# 34_14.net
KiCad netlist of a schematic drawn in Altium Designer
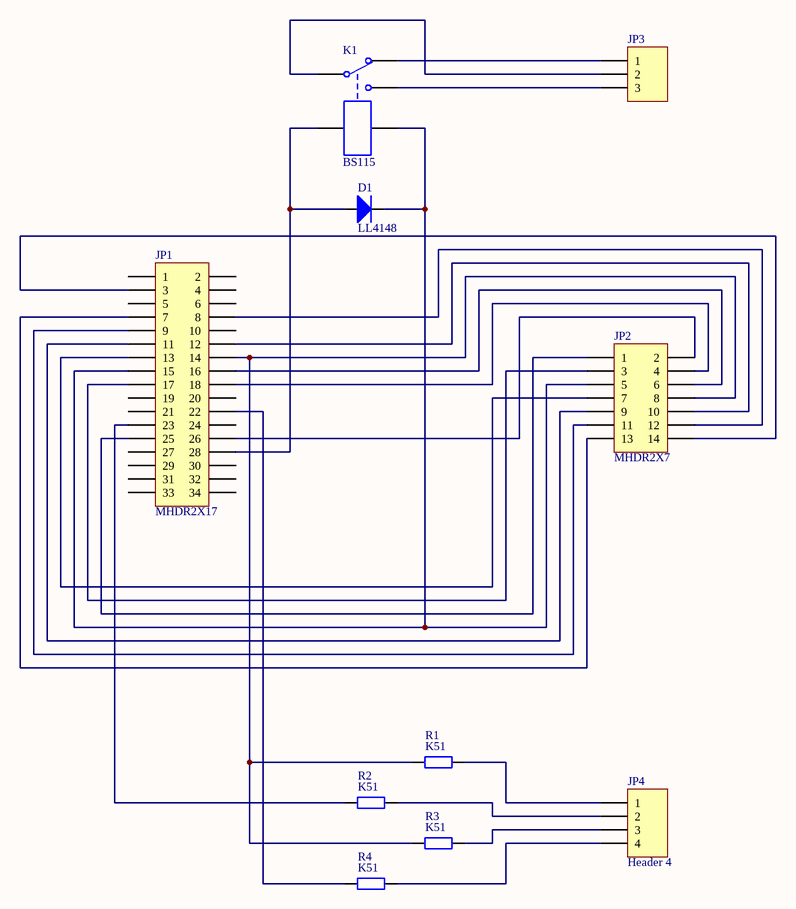
[diagram p0: 34_14.SchDoc]

(export (version "E")
  (design (tool "Eeschema 10.0.6"))
  (components
    (comp (ref "D1")
      (value "LL4148")
      (footprint "_1206d")
      (description "Diode")
      (fields (field (name "MANUFACTURER") "Generic Components") (field (name "PUBLISHER") "Altium Limited"))
      (libsource (lib "PAL") (part "Diode"))
    )
    (comp (ref "JP1")
      (value "MHDR2X17")
      (footprint "HDR2X17")
      (description "Header, 17-Pin, Dual row")
      (fields (field (name "MANUFACTURER") "Generic Components") (field (name "PUBLISHER") "Altium Limited"))
      (libsource (lib "Miscellaneous Connectors") (part "MHDR2X17"))
    )
    (comp (ref "JP2")
      (value "MHDR2X7")
      (footprint "HDR2X7")
      (description "Header, 7-Pin, Dual row")
      (fields (field (name "MANUFACTURER") "Generic Components") (field (name "PUBLISHER") "Altium Limited"))
      (libsource (lib "Miscellaneous Connectors") (part "MHDR2X7"))
    )
    (comp (ref "JP3")
      (value "Header 3")
      (footprint "2EDG-5.08-3P")
      (description "Header, 3-Pin")
      (fields (field (name "MANUFACTURER") "Generic Components") (field (name "PUBLISHER") "Altium Limited"))
      (libsource (lib "Miscellaneous Connectors") (part "Header 3"))
    )
    (comp (ref "JP4")
      (value "Header 4")
      (footprint "2EDG-5.08-4P - duplicate")
      (description "Header, 4-Pin")
      (fields (field (name "MANUFACTURER") "Generic Components") (field (name "PUBLISHER") "Altium Limited"))
      (libsource (lib "Miscellaneous Connectors") (part "Header 4"))
    )
    (comp (ref "K1")
      (value "BS115")
      (footprint "bs115")
      (description "Single-Pole Dual-Throw Relay")
      (fields (field (name "MANUFACTURER") "Generic Components") (field (name "PUBLISHER") "Altium Limited"))
      (libsource (lib "PAL") (part "BS115"))
    )
    (comp (ref "R1")
      (value "K51")
      (footprint "_1206")
      (description "Resistor")
      (fields (field (name "MANUFACTURER") "Generic Components") (field (name "PUBLISHER") "Altium Limited"))
      (libsource (lib "Miscellaneous Devices") (part "Res2"))
    )
    (comp (ref "R2")
      (value "K51")
      (footprint "_1206")
      (description "Resistor")
      (fields (field (name "MANUFACTURER") "Generic Components") (field (name "PUBLISHER") "Altium Limited"))
      (libsource (lib "Miscellaneous Devices") (part "Res2"))
    )
    (comp (ref "R3")
      (value "K51")
      (footprint "_1206")
      (description "Resistor")
      (fields (field (name "MANUFACTURER") "Generic Components") (field (name "PUBLISHER") "Altium Limited"))
      (libsource (lib "Miscellaneous Devices") (part "Res2"))
    )
    (comp (ref "R4")
      (value "K51")
      (footprint "_1206")
      (description "Resistor")
      (fields (field (name "MANUFACTURER") "Generic Components") (field (name "PUBLISHER") "Altium Limited"))
      (libsource (lib "Miscellaneous Devices") (part "Res2"))
    )
  )
  (nets
    (net (code "1") (name "Net-(D1-A)") (class "Default")
      (node (ref "D1") (pin "1") (pinfunction "A_1") (pintype "passive"))
      (node (ref "JP1") (pin "28") (pinfunction "28_28") (pintype "passive"))
      (node (ref "K1") (pin "4") (pinfunction "4_4") (pintype "passive"))
    )
    (net (code "2") (name "Net-(D1-K)") (class "Default")
      (node (ref "D1") (pin "2") (pinfunction "K_2") (pintype "passive"))
      (node (ref "JP1") (pin "15") (pinfunction "15_15") (pintype "passive"))
      (node (ref "JP2") (pin "5") (pinfunction "5_5") (pintype "passive"))
      (node (ref "K1") (pin "5") (pinfunction "5_5") (pintype "passive"))
    )
    (net (code "3") (name "Net-(JP1-Pad3)") (class "Default")
      (node (ref "JP1") (pin "3") (pinfunction "3_3") (pintype "passive"))
      (node (ref "JP2") (pin "14") (pinfunction "14_14") (pintype "passive"))
    )
    (net (code "4") (name "Net-(JP1-Pad7)") (class "Default")
      (node (ref "JP1") (pin "7") (pinfunction "7_7") (pintype "passive"))
      (node (ref "JP2") (pin "13") (pinfunction "13_13") (pintype "passive"))
    )
    (net (code "5") (name "Net-(JP1-Pad8)") (class "Default")
      (node (ref "JP1") (pin "8") (pinfunction "8_8") (pintype "passive"))
      (node (ref "JP2") (pin "12") (pinfunction "12_12") (pintype "passive"))
    )
    (net (code "6") (name "Net-(JP1-Pad9)") (class "Default")
      (node (ref "JP1") (pin "9") (pinfunction "9_9") (pintype "passive"))
      (node (ref "JP2") (pin "11") (pinfunction "11_11") (pintype "passive"))
    )
    (net (code "7") (name "Net-(JP1-Pad11)") (class "Default")
      (node (ref "JP1") (pin "11") (pinfunction "11_11") (pintype "passive"))
      (node (ref "JP2") (pin "9") (pinfunction "9_9") (pintype "passive"))
    )
    (net (code "8") (name "Net-(JP1-Pad12)") (class "Default")
      (node (ref "JP1") (pin "12") (pinfunction "12_12") (pintype "passive"))
      (node (ref "JP2") (pin "10") (pinfunction "10_10") (pintype "passive"))
    )
    (net (code "9") (name "Net-(JP1-Pad13)") (class "Default")
      (node (ref "JP1") (pin "13") (pinfunction "13_13") (pintype "passive"))
      (node (ref "JP2") (pin "7") (pinfunction "7_7") (pintype "passive"))
    )
    (net (code "10") (name "Net-(JP1-Pad14)") (class "Default")
      (node (ref "JP1") (pin "14") (pinfunction "14_14") (pintype "passive"))
      (node (ref "JP2") (pin "8") (pinfunction "8_8") (pintype "passive"))
      (node (ref "R1") (pin "1") (pinfunction "1_1") (pintype "passive"))
      (node (ref "R3") (pin "1") (pinfunction "1_1") (pintype "passive"))
    )
    (net (code "11") (name "Net-(JP1-Pad16)") (class "Default")
      (node (ref "JP1") (pin "16") (pinfunction "16_16") (pintype "passive"))
      (node (ref "JP2") (pin "6") (pinfunction "6_6") (pintype "passive"))
    )
    (net (code "12") (name "Net-(JP1-Pad17)") (class "Default")
      (node (ref "JP1") (pin "17") (pinfunction "17_17") (pintype "passive"))
      (node (ref "JP2") (pin "3") (pinfunction "3_3") (pintype "passive"))
    )
    (net (code "13") (name "Net-(JP1-Pad18)") (class "Default")
      (node (ref "JP1") (pin "18") (pinfunction "18_18") (pintype "passive"))
      (node (ref "JP2") (pin "4") (pinfunction "4_4") (pintype "passive"))
    )
    (net (code "14") (name "Net-(JP1-Pad22)") (class "Default")
      (node (ref "JP1") (pin "22") (pinfunction "22_22") (pintype "passive"))
      (node (ref "R4") (pin "1") (pinfunction "1_1") (pintype "passive"))
    )
    (net (code "15") (name "Net-(JP1-Pad23)") (class "Default")
      (node (ref "JP1") (pin "23") (pinfunction "23_23") (pintype "passive"))
      (node (ref "R2") (pin "1") (pinfunction "1_1") (pintype "passive"))
    )
    (net (code "16") (name "Net-(JP1-Pad25)") (class "Default")
      (node (ref "JP1") (pin "25") (pinfunction "25_25") (pintype "passive"))
      (node (ref "JP2") (pin "1") (pinfunction "1_1") (pintype "passive"))
    )
    (net (code "17") (name "Net-(JP1-Pad26)") (class "Default")
      (node (ref "JP1") (pin "26") (pinfunction "26_26") (pintype "passive"))
      (node (ref "JP2") (pin "2") (pinfunction "2_2") (pintype "passive"))
    )
    (net (code "18") (name "Net-(JP3-Pad1)") (class "Default")
      (node (ref "JP3") (pin "1") (pinfunction "1_1") (pintype "passive"))
      (node (ref "K1") (pin "2") (pinfunction "2_2") (pintype "passive"))
    )
    (net (code "19") (name "Net-(JP3-Pad2)") (class "Default")
      (node (ref "JP3") (pin "2") (pinfunction "2_2") (pintype "passive"))
      (node (ref "K1") (pin "1") (pinfunction "1_1") (pintype "passive"))
    )
    (net (code "20") (name "Net-(JP3-Pad3)") (class "Default")
      (node (ref "JP3") (pin "3") (pinfunction "3_3") (pintype "passive"))
      (node (ref "K1") (pin "3") (pinfunction "3_3") (pintype "passive"))
    )
    (net (code "21") (name "Net-(JP4-Pad1)") (class "Default")
      (node (ref "JP4") (pin "1") (pinfunction "1_1") (pintype "passive"))
      (node (ref "R1") (pin "2") (pinfunction "2_2") (pintype "passive"))
    )
    (net (code "22") (name "Net-(JP4-Pad2)") (class "Default")
      (node (ref "JP4") (pin "2") (pinfunction "2_2") (pintype "passive"))
      (node (ref "R2") (pin "2") (pinfunction "2_2") (pintype "passive"))
    )
    (net (code "23") (name "Net-(JP4-Pad3)") (class "Default")
      (node (ref "JP4") (pin "3") (pinfunction "3_3") (pintype "passive"))
      (node (ref "R3") (pin "2") (pinfunction "2_2") (pintype "passive"))
    )
    (net (code "24") (name "Net-(JP4-Pad4)") (class "Default")
      (node (ref "JP4") (pin "4") (pinfunction "4_4") (pintype "passive"))
      (node (ref "R4") (pin "2") (pinfunction "2_2") (pintype "passive"))
    )
    (net (code "25") (name "unconnected-(JP1-Pad1)") (class "Default")
      (node (ref "JP1") (pin "1") (pinfunction "1_1") (pintype "passive"))
    )
    (net (code "26") (name "unconnected-(JP1-Pad2)") (class "Default")
      (node (ref "JP1") (pin "2") (pinfunction "2_2") (pintype "passive"))
    )
    (net (code "27") (name "unconnected-(JP1-Pad4)") (class "Default")
      (node (ref "JP1") (pin "4") (pinfunction "4_4") (pintype "passive"))
    )
    (net (code "28") (name "unconnected-(JP1-Pad5)") (class "Default")
      (node (ref "JP1") (pin "5") (pinfunction "5_5") (pintype "passive"))
    )
    (net (code "29") (name "unconnected-(JP1-Pad6)") (class "Default")
      (node (ref "JP1") (pin "6") (pinfunction "6_6") (pintype "passive"))
    )
    (net (code "30") (name "unconnected-(JP1-Pad10)") (class "Default")
      (node (ref "JP1") (pin "10") (pinfunction "10_10") (pintype "passive"))
    )
    (net (code "31") (name "unconnected-(JP1-Pad19)") (class "Default")
      (node (ref "JP1") (pin "19") (pinfunction "19_19") (pintype "passive"))
    )
    (net (code "32") (name "unconnected-(JP1-Pad20)") (class "Default")
      (node (ref "JP1") (pin "20") (pinfunction "20_20") (pintype "passive"))
    )
    (net (code "33") (name "unconnected-(JP1-Pad21)") (class "Default")
      (node (ref "JP1") (pin "21") (pinfunction "21_21") (pintype "passive"))
    )
    (net (code "34") (name "unconnected-(JP1-Pad24)") (class "Default")
      (node (ref "JP1") (pin "24") (pinfunction "24_24") (pintype "passive"))
    )
    (net (code "35") (name "unconnected-(JP1-Pad27)") (class "Default")
      (node (ref "JP1") (pin "27") (pinfunction "27_27") (pintype "passive"))
    )
    (net (code "36") (name "unconnected-(JP1-Pad29)") (class "Default")
      (node (ref "JP1") (pin "29") (pinfunction "29_29") (pintype "passive"))
    )
    (net (code "37") (name "unconnected-(JP1-Pad30)") (class "Default")
      (node (ref "JP1") (pin "30") (pinfunction "30_30") (pintype "passive"))
    )
    (net (code "38") (name "unconnected-(JP1-Pad31)") (class "Default")
      (node (ref "JP1") (pin "31") (pinfunction "31_31") (pintype "passive"))
    )
    (net (code "39") (name "unconnected-(JP1-Pad32)") (class "Default")
      (node (ref "JP1") (pin "32") (pinfunction "32_32") (pintype "passive"))
    )
    (net (code "40") (name "unconnected-(JP1-Pad33)") (class "Default")
      (node (ref "JP1") (pin "33") (pinfunction "33_33") (pintype "passive"))
    )
    (net (code "41") (name "unconnected-(JP1-Pad34)") (class "Default")
      (node (ref "JP1") (pin "34") (pinfunction "34_34") (pintype "passive"))
    )
  )
)
